# fakel.net
KiCad netlist of a schematic drawn in Altium Designer
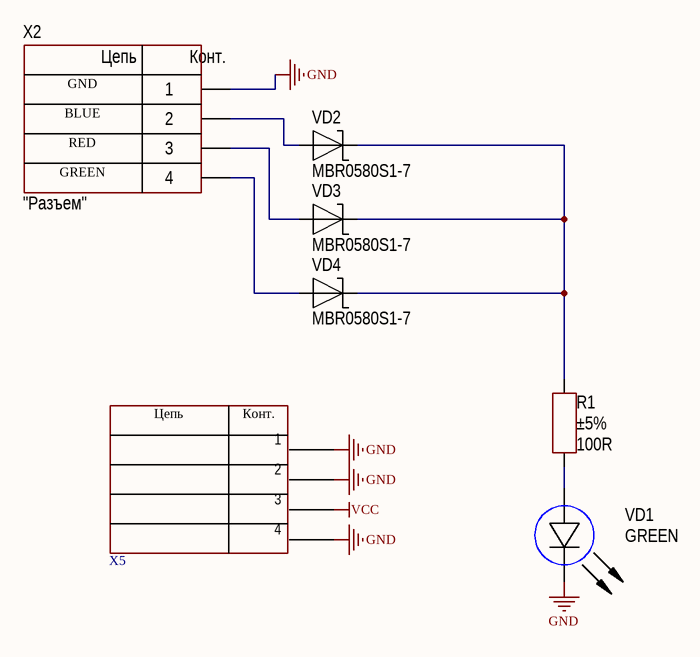
[diagram p0: fakel.SchDoc]

(export (version "E")
  (design (tool "Eeschema 10.0.6"))
  (components
    (comp (ref "R1")
      (value "100R")
      (footprint "RES: 0603")
      (fields
        (field (name "MANUFACTURER") "Yageo")
        (field (name "PARTNUMBER") "RC0603JR-07100RL")
        (field (name "VALUEMANUFACTURERPARTNUMBER") "Resistor film, 100R, ±5%, 0603, 0.1W, -55...+125°C")
        (field (name "TOLERANCE") "±5%")
      )
      (libsource (lib "Resistor") (part "Resistor_0603"))
    )
    (comp (ref "VD1")
      (value "~")
      (footprint "LED: 0805G")
      (fields
        (field (name "VALUEMANUFACTURERPARTNUMBER") "LED, *, *, *, -55...+150°C")
        (field (name "COLOR") "GREEN")
      )
      (libsource (lib "Diode") (part "LED_single"))
    )
    (comp (ref "VD2")
      (value "~")
      (footprint "DIODE: SOD523")
      (fields
        (field (name "MANUFACTURER") "Diodes Incorporated")
        (field (name "VALUEMANUFACTURERPARTNUMBER") "Schottky diode, 80V, 500mA, 1V, 15pF, SOD-123, -55...+150°C")
        (field (name "VOLTAGE") "80V")
        (field (name "PARTNUMBER") "MBR0580S1-7")
      )
      (libsource (lib "Diode") (part "Schottky_single"))
    )
    (comp (ref "VD3")
      (value "~")
      (footprint "DIODE: SOD523")
      (fields
        (field (name "MANUFACTURER") "Diodes Incorporated")
        (field (name "VALUEMANUFACTURERPARTNUMBER") "Schottky diode, 80V, 500mA, 1V, 15pF, SOD-123, -55...+150°C")
        (field (name "VOLTAGE") "80V")
        (field (name "PARTNUMBER") "MBR0580S1-7")
      )
      (libsource (lib "Diode") (part "Schottky_single"))
    )
    (comp (ref "VD4")
      (value "~")
      (footprint "DIODE: SOD523")
      (fields
        (field (name "MANUFACTURER") "Diodes Incorporated")
        (field (name "VALUEMANUFACTURERPARTNUMBER") "Schottky diode, 80V, 500mA, 1V, 15pF, SOD-123, -55...+150°C")
        (field (name "VOLTAGE") "80V")
        (field (name "PARTNUMBER") "MBR0580S1-7")
      )
      (libsource (lib "Diode") (part "Schottky_single"))
    )
    (comp (ref "X2")
      (value "~")
      (footprint "CON: PBS-4 R")
      (fields
        (field (name "MANUFACTURER") "Connfly")
        (field (name "VALUEMANUFACTURERPARTNUMBER") "Connector, 4pin, 2.54mm, 500VAC, 3A")
        (field (name "PARTNUMBER") "PBS-4")
        (field (name "COMMENTTEXT") "\"Разъем\"")
      )
      (libsource (lib "Connector") (part "PBS-4"))
    )
    (comp (ref "X5")
      (value "PBS-4 cut")
      (footprint "PBS-4 CUT")
      (libsource (lib "conect") (part "PBS-4 cut"))
    )
  )
  (nets
    (net (code "1") (name "GND") (class "Default")
      (node (ref "VD1") (pin "2") (pinfunction "C_2") (pintype "passive"))
      (node (ref "X2") (pin "1") (pinfunction "1_1") (pintype "passive"))
      (node (ref "X5") (pin "1") (pinfunction "1_1") (pintype "passive"))
      (node (ref "X5") (pin "2") (pinfunction "2_2") (pintype "passive"))
      (node (ref "X5") (pin "4") (pinfunction "4_4") (pintype "passive"))
    )
    (net (code "2") (name "Net-(R1-Pad2)") (class "Default")
      (node (ref "R1") (pin "2") (pinfunction "2_2") (pintype "passive"))
      (node (ref "VD2") (pin "2") (pinfunction "2_2") (pintype "passive"))
      (node (ref "VD3") (pin "2") (pinfunction "2_2") (pintype "passive"))
      (node (ref "VD4") (pin "2") (pinfunction "2_2") (pintype "passive"))
    )
    (net (code "3") (name "Net-(VD1-A)") (class "Default")
      (node (ref "R1") (pin "1") (pinfunction "1_1") (pintype "passive"))
      (node (ref "VD1") (pin "1") (pinfunction "A_1") (pintype "passive"))
    )
    (net (code "4") (name "Net-(VD2-Pad1)") (class "Default")
      (node (ref "VD2") (pin "1") (pinfunction "1_1") (pintype "passive"))
      (node (ref "X2") (pin "2") (pinfunction "2_2") (pintype "passive"))
    )
    (net (code "5") (name "Net-(VD3-Pad1)") (class "Default")
      (node (ref "VD3") (pin "1") (pinfunction "1_1") (pintype "passive"))
      (node (ref "X2") (pin "3") (pinfunction "3_3") (pintype "power_in"))
    )
    (net (code "6") (name "Net-(VD4-Pad1)") (class "Default")
      (node (ref "VD4") (pin "1") (pinfunction "1_1") (pintype "passive"))
      (node (ref "X2") (pin "4") (pinfunction "4_4") (pintype "power_in"))
    )
    (net (code "7") (name "VCC") (class "Default")
      (node (ref "X5") (pin "3") (pinfunction "3_3") (pintype "passive"))
    )
  )
)
